# usb.net
KiCad netlist of a schematic drawn in Altium Designer
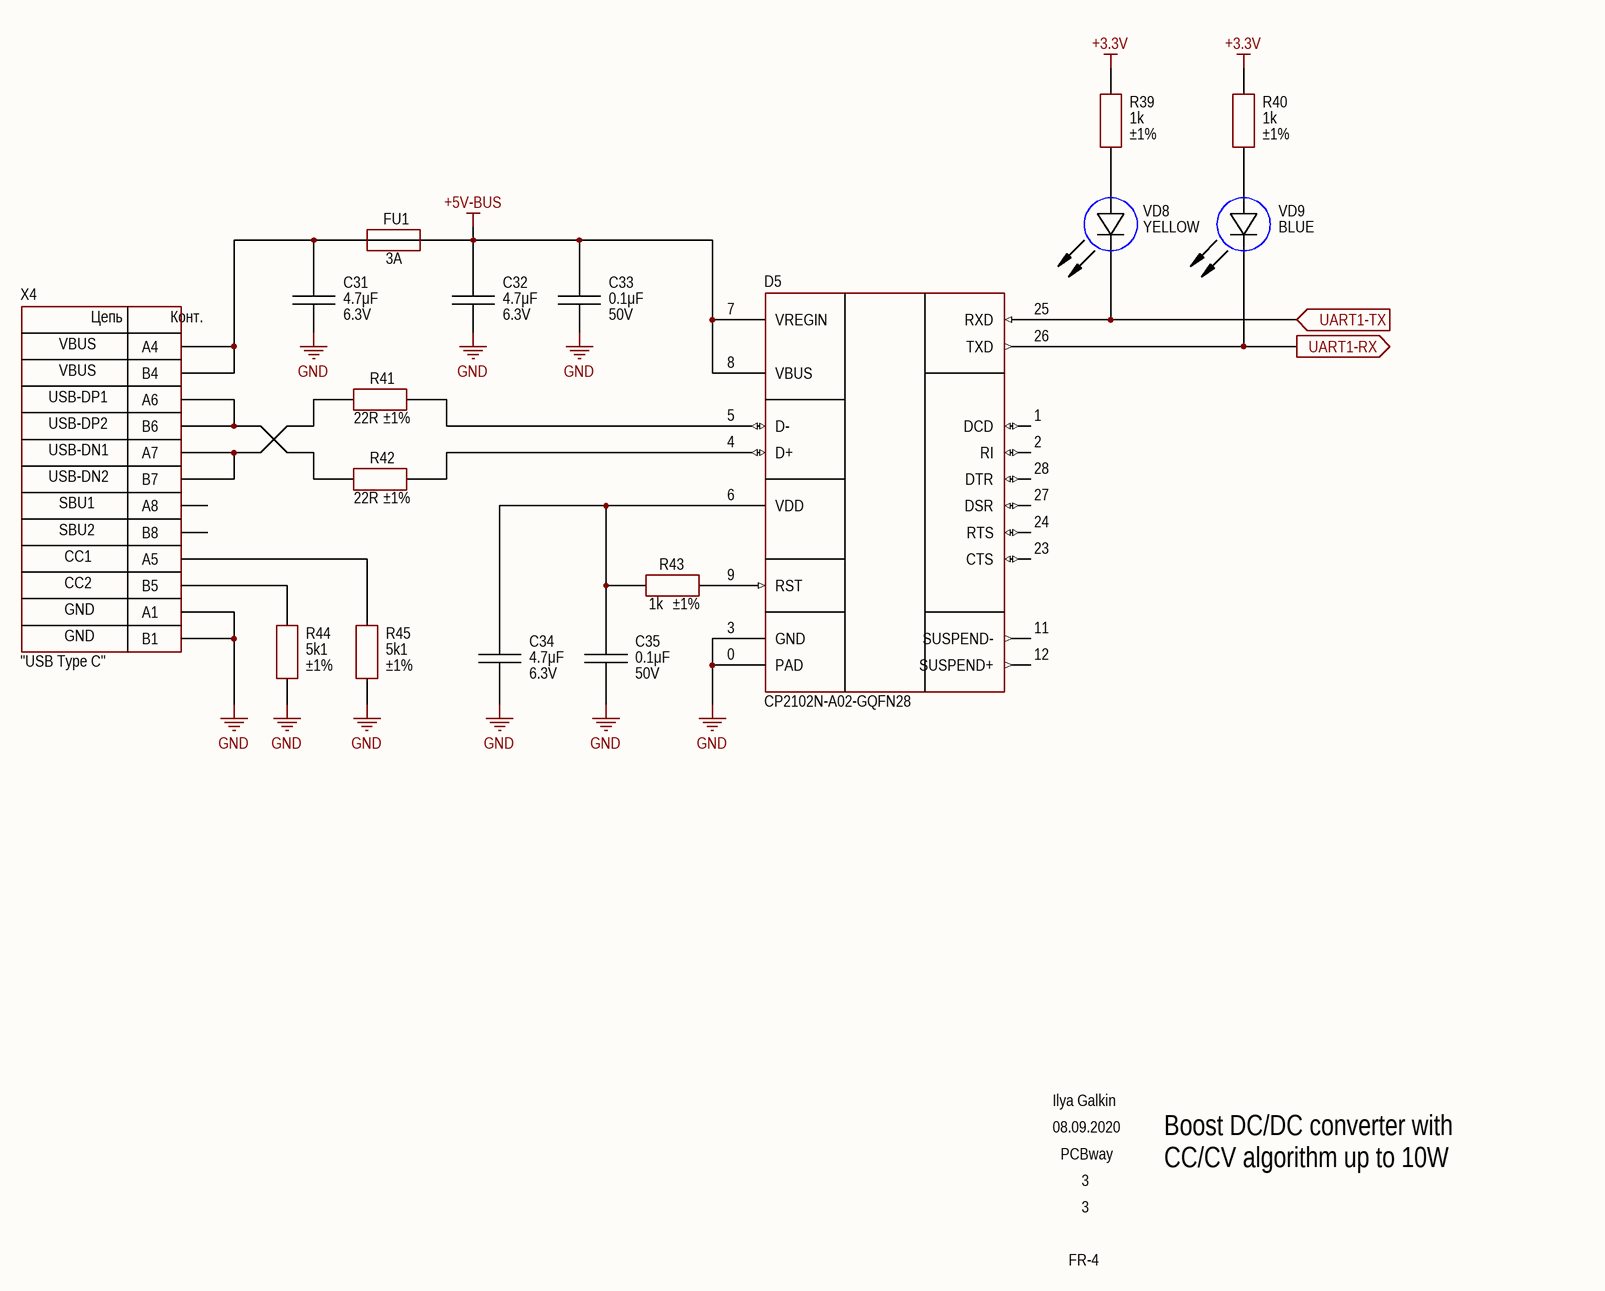
[diagram p0: usb.SchDoc]

(export (version "E")
  (design (tool "Eeschema 10.0.6"))
  (components
    (comp (ref "C31")
      (value "4.7μF")
      (footprint "CAP: 0603")
      (fields
        (field (name "MANUFACTURER") "Samsung")
        (field (name "PARTNUMBER") "CL10B475KQ8NQNC")
        (field (name "VALUEMANUFACTURERPARTNUMBER") "Ceramic capacitor, 4.7μF, X7R, ±10%, 6.3V, 0603, -55...+125°C")
        (field (name "VOLTAGE") "6.3V")
      )
      (libsource (lib "capacitor") (part "Ceramic_0603"))
    )
    (comp (ref "C32")
      (value "4.7μF")
      (footprint "CAP: 0603")
      (fields
        (field (name "MANUFACTURER") "Samsung")
        (field (name "PARTNUMBER") "CL10B475KQ8NQNC")
        (field (name "VALUEMANUFACTURERPARTNUMBER") "Ceramic capacitor, 4.7μF, X7R, ±10%, 6.3V, 0603, -55...+125°C")
        (field (name "VOLTAGE") "6.3V")
      )
      (libsource (lib "capacitor") (part "Ceramic_0603"))
    )
    (comp (ref "C33")
      (value "0.1μF")
      (footprint "CAP: 0603")
      (fields
        (field (name "MANUFACTURER") "Samsung")
        (field (name "PARTNUMBER") "CL10B104KB8NNNL")
        (field (name "VALUEMANUFACTURERPARTNUMBER") "Ceramic capacitor, 0.1μF, X7R, ±10%, 50V, 0603, -55...+125°C")
        (field (name "VOLTAGE") "50V")
      )
      (libsource (lib "capacitor") (part "Ceramic_0603"))
    )
    (comp (ref "C34")
      (value "4.7μF")
      (footprint "CAP: 0603")
      (fields
        (field (name "MANUFACTURER") "Samsung")
        (field (name "PARTNUMBER") "CL10B475KQ8NQNC")
        (field (name "VALUEMANUFACTURERPARTNUMBER") "Ceramic capacitor, 4.7μF, X7R, ±10%, 6.3V, 0603, -55...+125°C")
        (field (name "VOLTAGE") "6.3V")
      )
      (libsource (lib "capacitor") (part "Ceramic_0603"))
    )
    (comp (ref "C35")
      (value "0.1μF")
      (footprint "CAP: 0603")
      (fields
        (field (name "MANUFACTURER") "Samsung")
        (field (name "PARTNUMBER") "CL10B104KB8NNNL")
        (field (name "VALUEMANUFACTURERPARTNUMBER") "Ceramic capacitor, 0.1μF, X7R, ±10%, 50V, 0603, -55...+125°C")
        (field (name "VOLTAGE") "50V")
      )
      (libsource (lib "capacitor") (part "Ceramic_0603"))
    )
    (comp (ref "D5")
      (value "~")
      (footprint "28-QFN (5x5)")
      (description "USB-to-UART")
      (fields
        (field (name "MANUFACTURER") "Silicon Labs")
        (field (name "VALUEMANUFACTURERPARTNUMBER") "IC usb-to-uart bridge, USB2.0, 3...3.6V, -40...+85°C, 28-VFQFN")
        (field (name "PARTNUMBER") "CP2102N-A02-GQFN28")
      )
      (libsource (lib "ic-interface") (part "CP2102N"))
    )
    (comp (ref "FU1")
      (value "~")
      (footprint "FUSE: 1206")
      (fields
        (field (name "MANUFACTURER") "Panasonic")
        (field (name "VALUEMANUFACTURERPARTNUMBER") "Electromechanics relay, 32VDC, 3A, 1206 case, ")
        (field (name "PARTNUMBER") "ERB-RG3R00V")
        (field (name "MAXCURRENT") "3A")
      )
      (libsource (lib "electromechanics") (part "Fuse"))
    )
    (comp (ref "R39")
      (value "1k")
      (footprint "RES: 0603")
      (fields
        (field (name "MANUFACTURER") "Yageo")
        (field (name "PARTNUMBER") "RC0603FR-071KL")
        (field (name "VALUEMANUFACTURERPARTNUMBER") "Resistor film, 1k, ±1%, 0603, 0.1W, -55...+125°C")
        (field (name "TOLERANCE") "±1%")
      )
      (libsource (lib "") (part "Resistor_0603_1"))
    )
    (comp (ref "R40")
      (value "1k")
      (footprint "RES: 0603")
      (fields
        (field (name "MANUFACTURER") "Yageo")
        (field (name "PARTNUMBER") "RC0603FR-071KL")
        (field (name "VALUEMANUFACTURERPARTNUMBER") "Resistor film, 1k, ±1%, 0603, 0.1W, -55...+125°C")
        (field (name "TOLERANCE") "±1%")
      )
      (libsource (lib "") (part "Resistor_0603_1"))
    )
    (comp (ref "R41")
      (value "22R")
      (footprint "RES: 0603")
      (fields
        (field (name "MANUFACTURER") "Yageo")
        (field (name "PARTNUMBER") "RC0603FR-0722RL")
        (field (name "VALUEMANUFACTURERPARTNUMBER") "Resistor film, 22R, ±1%, 0603, 0.1W, -55...+125°C")
        (field (name "TOLERANCE") "±1%")
      )
      (libsource (lib "Resistor") (part "Resistor_0603"))
    )
    (comp (ref "R42")
      (value "22R")
      (footprint "RES: 0603")
      (fields
        (field (name "MANUFACTURER") "Yageo")
        (field (name "PARTNUMBER") "RC0603FR-0722RL")
        (field (name "VALUEMANUFACTURERPARTNUMBER") "Resistor film, 22R, ±1%, 0603, 0.1W, -55...+125°C")
        (field (name "TOLERANCE") "±1%")
      )
      (libsource (lib "Resistor") (part "Resistor_0603"))
    )
    (comp (ref "R43")
      (value "1k")
      (footprint "RES: 0603")
      (fields
        (field (name "MANUFACTURER") "Yageo")
        (field (name "PARTNUMBER") "RC0603FR-071KL")
        (field (name "VALUEMANUFACTURERPARTNUMBER") "Resistor film, 1k, ±1%, 0603, 0.1W, -55...+125°C")
        (field (name "TOLERANCE") "±1%")
      )
      (libsource (lib "resistor") (part "Resistor_0603"))
    )
    (comp (ref "R44")
      (value "5k1")
      (footprint "RES: 0603")
      (fields
        (field (name "MANUFACTURER") "Yageo")
        (field (name "PARTNUMBER") "RC0603FR-075K1L")
        (field (name "VALUEMANUFACTURERPARTNUMBER") "Resistor film, 5k1, ±1%, 0603, 0.1W, -55...+125°C")
        (field (name "TOLERANCE") "±1%")
      )
      (libsource (lib "") (part "Resistor_0603_1"))
    )
    (comp (ref "R45")
      (value "5k1")
      (footprint "RES: 0603")
      (fields
        (field (name "MANUFACTURER") "Yageo")
        (field (name "PARTNUMBER") "RC0603FR-075K1L")
        (field (name "VALUEMANUFACTURERPARTNUMBER") "Resistor film, 5k1, ±1%, 0603, 0.1W, -55...+125°C")
        (field (name "TOLERANCE") "±1%")
      )
      (libsource (lib "") (part "Resistor_0603_1"))
    )
    (comp (ref "VD8")
      (value "~")
      (footprint "LED: 0603Y")
      (fields
        (field (name "MANUFACTURER") "Wurth")
        (field (name "VALUEMANUFACTURERPARTNUMBER") "LED, 20mA, 2V, 0603, -55...+150°C")
        (field (name "PARTNUMBER") "150060YS75000")
        (field (name "COLOR") "YELLOW")
      )
      (libsource (lib "Diode") (part "LED_single"))
    )
    (comp (ref "VD9")
      (value "~")
      (footprint "LED: 0603B")
      (fields
        (field (name "MANUFACTURER") "Wurth")
        (field (name "VALUEMANUFACTURERPARTNUMBER") "LED, 20mA, 3.2V, 0603, -55...+150°C")
        (field (name "PARTNUMBER") "150060BS75000")
        (field (name "COLOR") "BLUE")
      )
      (libsource (lib "Diode") (part "LED_single"))
    )
    (comp (ref "X4")
      (value "~")
      (footprint "CON: TYPE-C-31-M-12")
      (fields
        (field (name "MANUFACTURER") "Korean Hroparts")
        (field (name "VALUEMANUFACTURERPARTNUMBER") "USB Type C, 3A")
        (field (name "PARTNUMBER") "TYPE-C-31-M-12")
        (field (name "COMMENTTEXT") "\"USB Type C\"")
      )
      (libsource (lib "connector") (part "Connector_USB_Type_C"))
    )
  )
  (nets
    (net (code "1") (name "+3.3V") (class "Default")
      (node (ref "R39") (pin "2") (pinfunction "2_2") (pintype "passive"))
      (node (ref "R40") (pin "2") (pinfunction "2_2") (pintype "passive"))
    )
    (net (code "2") (name "+5V-BUS") (class "Default")
      (node (ref "C32") (pin "2") (pinfunction "2_2") (pintype "passive"))
      (node (ref "C33") (pin "2") (pinfunction "2_2") (pintype "passive"))
      (node (ref "D5") (pin "7") (pinfunction "VREGIN_7") (pintype "passive"))
      (node (ref "D5") (pin "8") (pinfunction "VBUS_8") (pintype "passive"))
      (node (ref "FU1") (pin "2") (pinfunction "2_2") (pintype "passive"))
    )
    (net (code "3") (name "/UART1-RX") (class "Default")
      (node (ref "D5") (pin "26") (pinfunction "TXD_26") (pintype "output"))
      (node (ref "VD9") (pin "2") (pinfunction "C_2") (pintype "passive"))
    )
    (net (code "4") (name "/UART1-TX") (class "Default")
      (node (ref "D5") (pin "25") (pinfunction "RXD_25") (pintype "input"))
      (node (ref "VD8") (pin "2") (pinfunction "C_2") (pintype "passive"))
    )
    (net (code "5") (name "GND") (class "Default")
      (node (ref "C31") (pin "1") (pinfunction "1_1") (pintype "passive"))
      (node (ref "C32") (pin "1") (pinfunction "1_1") (pintype "passive"))
      (node (ref "C33") (pin "1") (pinfunction "1_1") (pintype "passive"))
      (node (ref "C34") (pin "1") (pinfunction "1_1") (pintype "passive"))
      (node (ref "C35") (pin "1") (pinfunction "1_1") (pintype "passive"))
      (node (ref "D5") (pin "0") (pinfunction "PAD_0") (pintype "passive"))
      (node (ref "D5") (pin "3") (pinfunction "GND_3") (pintype "passive"))
      (node (ref "R44") (pin "1") (pinfunction "1_1") (pintype "passive"))
      (node (ref "R45") (pin "1") (pinfunction "1_1") (pintype "passive"))
      (node (ref "X4") (pin "A1") (pinfunction "A1_A1") (pintype "power_in"))
      (node (ref "X4") (pin "B1") (pinfunction "B1_B1") (pintype "power_in"))
    )
    (net (code "6") (name "Net-(C31-Pad2)") (class "Default")
      (node (ref "C31") (pin "2") (pinfunction "2_2") (pintype "passive"))
      (node (ref "FU1") (pin "1") (pinfunction "1_1") (pintype "passive"))
      (node (ref "X4") (pin "A4") (pinfunction "A4_A4") (pintype "passive"))
      (node (ref "X4") (pin "B4") (pinfunction "B4_B4") (pintype "passive"))
    )
    (net (code "7") (name "Net-(D5-D+)") (class "Default")
      (node (ref "D5") (pin "4") (pinfunction "D+_4") (pintype "bidirectional"))
      (node (ref "R42") (pin "1") (pinfunction "1_1") (pintype "passive"))
    )
    (net (code "8") (name "Net-(D5-D-)") (class "Default")
      (node (ref "D5") (pin "5") (pinfunction "D-_5") (pintype "bidirectional"))
      (node (ref "R41") (pin "1") (pinfunction "1_1") (pintype "passive"))
    )
    (net (code "9") (name "Net-(D5-RST)") (class "Default")
      (node (ref "D5") (pin "9") (pinfunction "RST_9") (pintype "input"))
      (node (ref "R43") (pin "2") (pinfunction "2_2") (pintype "passive"))
    )
    (net (code "10") (name "Net-(D5-VDD)") (class "Default")
      (node (ref "C34") (pin "2") (pinfunction "2_2") (pintype "passive"))
      (node (ref "C35") (pin "2") (pinfunction "2_2") (pintype "passive"))
      (node (ref "D5") (pin "6") (pinfunction "VDD_6") (pintype "passive"))
      (node (ref "R43") (pin "1") (pinfunction "1_1") (pintype "passive"))
    )
    (net (code "11") (name "Net-(R41-Pad2)") (class "Default")
      (node (ref "R41") (pin "2") (pinfunction "2_2") (pintype "passive"))
      (node (ref "X4") (pin "A7") (pinfunction "A7_A7") (pintype "power_in"))
      (node (ref "X4") (pin "B7") (pinfunction "B7_B7") (pintype "power_in"))
    )
    (net (code "12") (name "Net-(R42-Pad2)") (class "Default")
      (node (ref "R42") (pin "2") (pinfunction "2_2") (pintype "passive"))
      (node (ref "X4") (pin "A6") (pinfunction "A6_A6") (pintype "power_in"))
      (node (ref "X4") (pin "B6") (pinfunction "B6_B6") (pintype "power_in"))
    )
    (net (code "13") (name "Net-(R44-Pad2)") (class "Default")
      (node (ref "R44") (pin "2") (pinfunction "2_2") (pintype "passive"))
      (node (ref "X4") (pin "B5") (pinfunction "B5_B5") (pintype "power_in"))
    )
    (net (code "14") (name "Net-(R45-Pad2)") (class "Default")
      (node (ref "R45") (pin "2") (pinfunction "2_2") (pintype "passive"))
      (node (ref "X4") (pin "A5") (pinfunction "A5_A5") (pintype "power_in"))
    )
    (net (code "15") (name "Net-(VD8-A)") (class "Default")
      (node (ref "R39") (pin "1") (pinfunction "1_1") (pintype "passive"))
      (node (ref "VD8") (pin "1") (pinfunction "A_1") (pintype "passive"))
    )
    (net (code "16") (name "Net-(VD9-A)") (class "Default")
      (node (ref "R40") (pin "1") (pinfunction "1_1") (pintype "passive"))
      (node (ref "VD9") (pin "1") (pinfunction "A_1") (pintype "passive"))
    )
    (net (code "17") (name "unconnected-(D5-CTS-Pad23)") (class "Default")
      (node (ref "D5") (pin "23") (pinfunction "CTS_23") (pintype "bidirectional"))
    )
    (net (code "18") (name "unconnected-(D5-DCD-Pad1)") (class "Default")
      (node (ref "D5") (pin "1") (pinfunction "DCD_1") (pintype "bidirectional"))
    )
    (net (code "19") (name "unconnected-(D5-DSR-Pad27)") (class "Default")
      (node (ref "D5") (pin "27") (pinfunction "DSR_27") (pintype "bidirectional"))
    )
    (net (code "20") (name "unconnected-(D5-DTR-Pad28)") (class "Default")
      (node (ref "D5") (pin "28") (pinfunction "DTR_28") (pintype "bidirectional"))
    )
    (net (code "21") (name "unconnected-(D5-RI-Pad2)") (class "Default")
      (node (ref "D5") (pin "2") (pinfunction "RI_2") (pintype "bidirectional"))
    )
    (net (code "22") (name "unconnected-(D5-RTS-Pad24)") (class "Default")
      (node (ref "D5") (pin "24") (pinfunction "RTS_24") (pintype "bidirectional"))
    )
    (net (code "23") (name "unconnected-(D5-SUSPEND+-Pad12)") (class "Default")
      (node (ref "D5") (pin "12") (pinfunction "SUSPEND+_12") (pintype "output"))
    )
    (net (code "24") (name "unconnected-(D5-SUSPEND--Pad11)") (class "Default")
      (node (ref "D5") (pin "11") (pinfunction "SUSPEND-_11") (pintype "output"))
    )
    (net (code "25") (name "unconnected-(X4-PadA8)") (class "Default")
      (node (ref "X4") (pin "A8") (pinfunction "A8_A8") (pintype "power_in"))
    )
    (net (code "26") (name "unconnected-(X4-PadB8)") (class "Default")
      (node (ref "X4") (pin "B8") (pinfunction "B8_B8") (pintype "power_in"))
    )
  )
)
